# design.net
KiCad netlist of a schematic drawn in EasyEDA Pro
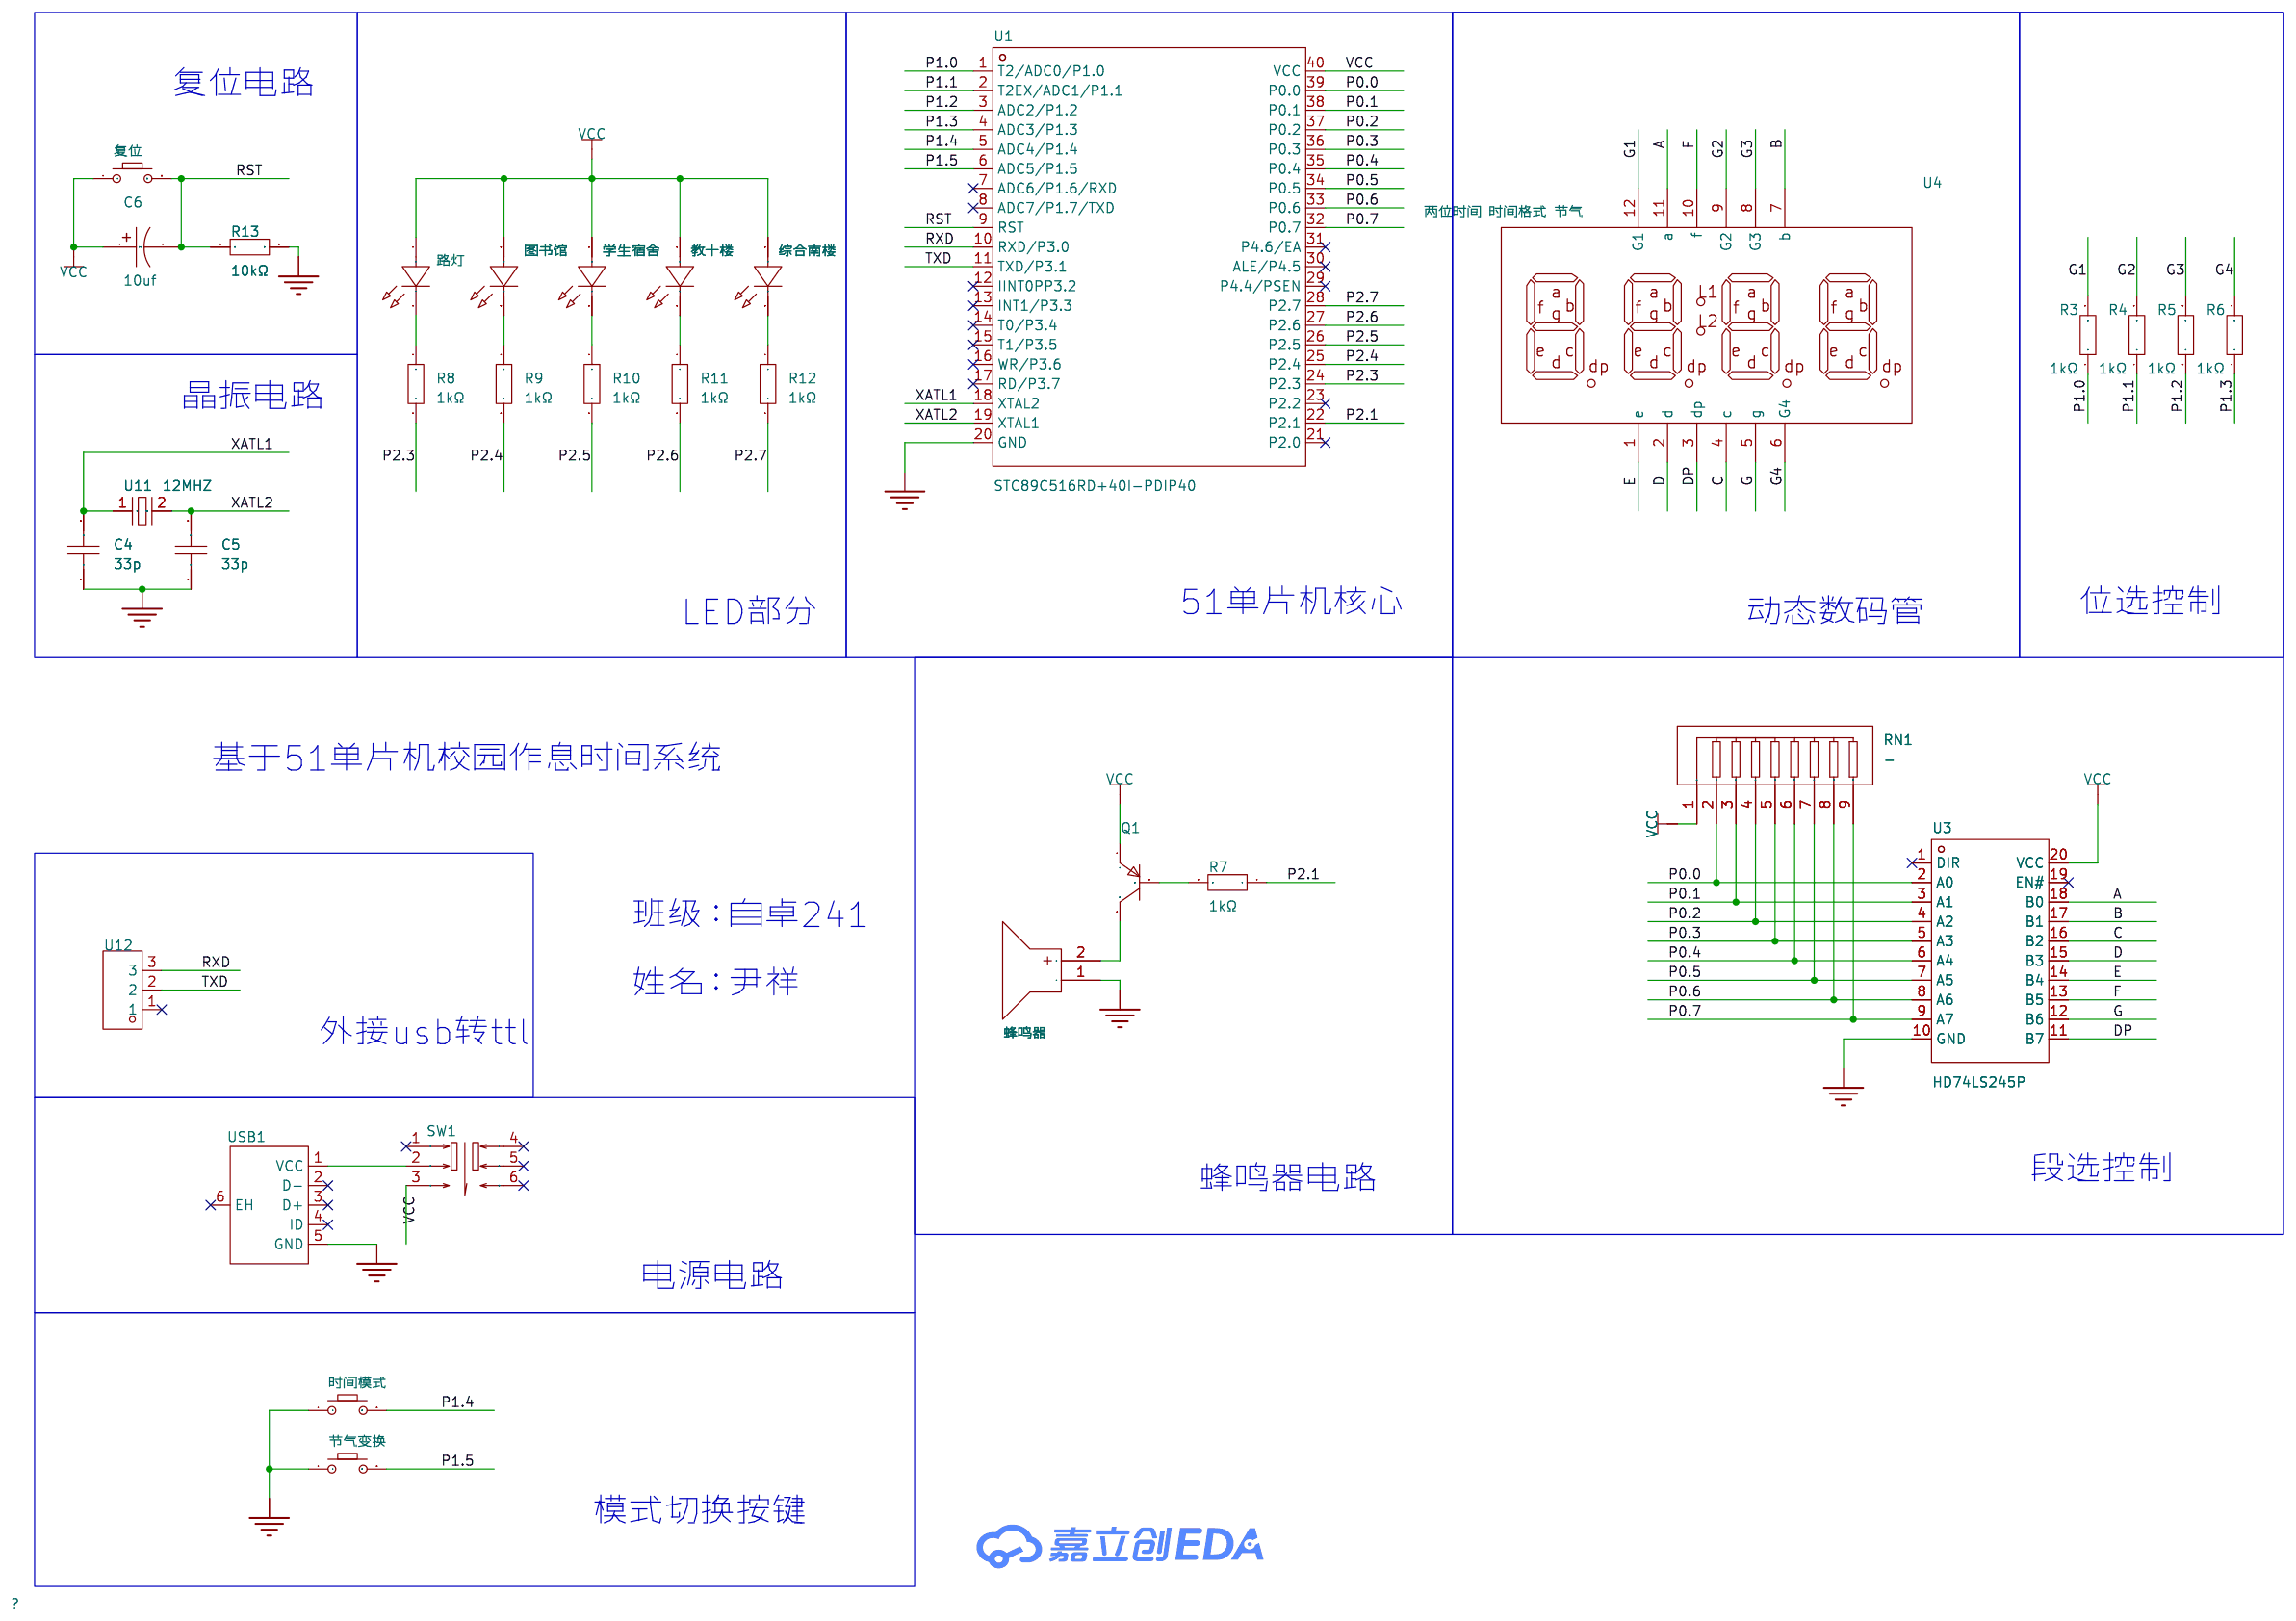
[diagram p0: schematic sheet]

(export (version "E")
  (design (tool "Eeschema 10.0.6"))
  (components
    (comp (ref "C4")
      (value "33p")
      (footprint "easyedapro:CAP-TH_L10.0-W4.5-P7.50-D0.6")
      (description "容值:-;额定电压:-;")
      (fields (field (name "Manufacturer Part") "250V 0.1uF 5% CBB电容"))
      (libsource (lib "easyedapro") (part "250V 0.1UF 5% CBBCapacitor"))
    )
    (comp (ref "C5")
      (value "33p")
      (footprint "easyedapro:CAP-TH_L10.0-W4.5-P7.50-D0.6")
      (description "容值:-;额定电压:-;")
      (fields (field (name "Manufacturer Part") "250V 0.1uF 5% CBB电容"))
      (libsource (lib "easyedapro") (part "250V 0.1UF 5% CBBCapacitor"))
    )
    (comp (ref "C6")
      (value "10uf")
      (footprint "easyedapro:CAP-TH_BD10.0-P5.00-D0.6-FD")
      (libsource (lib "easyedapro") (part "LF221M1HBKJ1013VGN"))
    )
    (comp (ref "Q1")
      (value "~")
      (footprint "easyedapro:S8550P_TO-92")
      (libsource (lib "easyedapro") (part "S8550_TO_PNP"))
    )
    (comp (ref "R3") (value "1kΩ") (footprint "easyedapro:R0603") (libsource (lib "easyedapro") (part "电阻")))
    (comp (ref "R4") (value "1kΩ") (footprint "easyedapro:R0603") (libsource (lib "easyedapro") (part "电阻")))
    (comp (ref "R5") (value "1kΩ") (footprint "easyedapro:R0603") (libsource (lib "easyedapro") (part "电阻")))
    (comp (ref "R6") (value "1kΩ") (footprint "easyedapro:R0603") (libsource (lib "easyedapro") (part "电阻")))
    (comp (ref "R7") (value "1kΩ") (footprint "easyedapro:R0603") (libsource (lib "easyedapro") (part "电阻")))
    (comp (ref "R8") (value "1kΩ") (footprint "easyedapro:R0603") (libsource (lib "easyedapro") (part "电阻")))
    (comp (ref "R9") (value "1kΩ") (footprint "easyedapro:R0603") (libsource (lib "easyedapro") (part "电阻")))
    (comp (ref "R10") (value "1kΩ") (footprint "easyedapro:R0603") (libsource (lib "easyedapro") (part "电阻")))
    (comp (ref "R11") (value "1kΩ") (footprint "easyedapro:R0603") (libsource (lib "easyedapro") (part "电阻")))
    (comp (ref "R12") (value "1kΩ") (footprint "easyedapro:R0603") (libsource (lib "easyedapro") (part "电阻")))
    (comp (ref "R13")
      (value "10kΩ")
      (footprint "easyedapro:R0603")
      (libsource (lib "easyedapro") (part "电阻"))
    )
    (comp (ref "RN1")
      (value "-")
      (footprint "easyedapro:RES-ARRAY-TH_9P-P2.54-D1.0")
      (description "电阻器数:-;阻值:-;单个元件功率:-;")
      (fields (field (name "Manufacturer Part") "排阻 10 K 5%"))
      (libsource (lib "easyedapro") (part "10 K 5%"))
    )
    (comp (ref "SW1")
      (value "SP-2212")
      (footprint "easyedapro:SW-TH_6P-L7.2-W7.2-P2.00-LS5.0")
      (description "电路结构:双刀双掷;自锁/无锁:自锁;安装方式:直插;触点电流:100mA;额定电压 (DC):30V;作用力:230gf;机械寿命:1.2万次;")
      (fields (field (name "Manufacturer") "RISHENG(日昇)"))
      (libsource (lib "easyedapro") (part "SP-2212"))
    )
    (comp (ref "U1")
      (value "STC89C516RD+40I-PDIP40")
      (footprint "easyedapro:DIP-40_L52.3-W13.9-P2.54-LS15.2-BL")
      (description "CPU内核:51系列;程序存储容量:61KB;RAM总容量:1.25KB;GPIO端口数量:35;工作电压范围:3.5V~5.5V;CPU最大主频:-;程序存储器类型:FLASH;")
      (fields (field (name "Manufacturer") "STC(宏晶)"))
      (libsource (lib "easyedapro") (part "STC89C516RD+40I-PDIP40"))
    )
    (comp (ref "U3")
      (value "HD74LS245P")
      (footprint "easyedapro:DIP-20_L26.8-W6.4-P2.54-LS7.6-BL")
      (fields (field (name "Manufacturer") "RENESAS(瑞萨)/IDT"))
      (libsource (lib "easyedapro") (part "HD74LS245P"))
    )
    (comp (ref "U4")
      (value "两位时间 时间格式 节气")
      (footprint "easyedapro:LED-SEG-TH_12P-L32.1-W10.0-P12.7-S7.62-BL")
      (libsource (lib "easyedapro") (part "0.28 4位 数码管"))
    )
    (comp (ref "U11")
      (value "12MHZ")
      (footprint "easyedapro:HC-49S_L11.0-W4.7-P4.88")
      (libsource (lib "easyedapro") (part "直插晶振"))
    )
    (comp (ref "U12")
      (value "2.54MM间距单排插针3P/高度11mm")
      (footprint "easyedapro:HDR-TH_3P-P2.54-V-M")
      (libsource (lib "easyedapro") (part "2.54MM间距单排插针3P/高度11MM"))
    )
    (comp (ref "USB1")
      (value "~")
      (footprint "easyedapro:USB_Micro")
      (libsource (lib "easyedapro") (part "USB_Micro"))
    )
    (comp (ref "图书馆")
      (value "图书馆")
      (footprint "easyedapro:LED-TH_BD3.0-P2.54-FD")
      (libsource (lib "easyedapro") (part "3MMFIR"))
    )
    (comp (ref "复位")
      (value "~")
      (footprint "easyedapro:Key_TH_3.5x6x4.3")
      (libsource (lib "easyedapro") (part "Key_TH_3.5x6x4.3"))
    )
    (comp (ref "学生宿舍")
      (value "学生宿舍")
      (footprint "easyedapro:LED-TH_BD3.0-P2.54-FD")
      (libsource (lib "easyedapro") (part "3MMFIR"))
    )
    (comp (ref "打铃")
      (value "蜂鸣器")
      (footprint "easyedapro:BUZ-TH_BD12.0-P6.00-D0.9-RD")
      (fields (field (name "Manufacturer Part") "打铃"))
      (libsource (lib "easyedapro") (part "BUZZER"))
    )
    (comp (ref "教十楼")
      (value "教十楼")
      (footprint "easyedapro:LED-TH_BD3.0-P2.54-FD")
      (libsource (lib "easyedapro") (part "3MMFIR"))
    )
    (comp (ref "时间模式")
      (value "~")
      (footprint "easyedapro:Key_TH_3.5x6x4.3")
      (libsource (lib "easyedapro") (part "Key_TH_3.5x6x4.3"))
    )
    (comp (ref "综合南楼")
      (value "综合南楼")
      (footprint "easyedapro:LED-TH_BD3.0-P2.54-FD")
      (libsource (lib "easyedapro") (part "3MMFIR"))
    )
    (comp (ref "节气变换")
      (value "~")
      (footprint "easyedapro:Key_TH_3.5x6x4.3")
      (libsource (lib "easyedapro") (part "Key_TH_3.5x6x4.3"))
    )
    (comp (ref "路灯")
      (value "路灯")
      (footprint "easyedapro:LED-TH_BD3.0-P2.54-FD")
      (libsource (lib "easyedapro") (part "3MMFIR"))
    )
  )
  (nets
    (net (code "1") (name "/A") (class "Default")
      (node (ref "U3") (pin "18") (pinfunction "B0_18") (pintype "unspecified"))
      (node (ref "U4") (pin "11") (pinfunction "a_11") (pintype "input"))
    )
    (net (code "2") (name "/B") (class "Default")
      (node (ref "U3") (pin "17") (pinfunction "B1_17") (pintype "unspecified"))
      (node (ref "U4") (pin "7") (pinfunction "b_7") (pintype "input"))
    )
    (net (code "3") (name "/C") (class "Default")
      (node (ref "U3") (pin "16") (pinfunction "B2_16") (pintype "unspecified"))
      (node (ref "U4") (pin "4") (pinfunction "c_4") (pintype "input"))
    )
    (net (code "4") (name "/D") (class "Default")
      (node (ref "U3") (pin "15") (pinfunction "B3_15") (pintype "unspecified"))
      (node (ref "U4") (pin "2") (pinfunction "d_2") (pintype "input"))
    )
    (net (code "5") (name "/DP") (class "Default")
      (node (ref "U3") (pin "11") (pinfunction "B7_11") (pintype "unspecified"))
      (node (ref "U4") (pin "3") (pinfunction "dp_3") (pintype "input"))
    )
    (net (code "6") (name "/E") (class "Default")
      (node (ref "U3") (pin "14") (pinfunction "B4_14") (pintype "unspecified"))
      (node (ref "U4") (pin "1") (pinfunction "e_1") (pintype "input"))
    )
    (net (code "7") (name "/F") (class "Default")
      (node (ref "U3") (pin "13") (pinfunction "B5_13") (pintype "unspecified"))
      (node (ref "U4") (pin "10") (pinfunction "f_10") (pintype "input"))
    )
    (net (code "8") (name "/G") (class "Default")
      (node (ref "U3") (pin "12") (pinfunction "B6_12") (pintype "unspecified"))
      (node (ref "U4") (pin "5") (pinfunction "g_5") (pintype "input"))
    )
    (net (code "9") (name "/G1") (class "Default")
      (node (ref "R3") (pin "2") (pinfunction "2_2") (pintype "input"))
      (node (ref "U4") (pin "12") (pinfunction "G1_12") (pintype "input"))
    )
    (net (code "10") (name "/G2") (class "Default")
      (node (ref "R4") (pin "2") (pinfunction "2_2") (pintype "input"))
      (node (ref "U4") (pin "9") (pinfunction "G2_9") (pintype "input"))
    )
    (net (code "11") (name "/G3") (class "Default")
      (node (ref "R5") (pin "2") (pinfunction "2_2") (pintype "input"))
      (node (ref "U4") (pin "8") (pinfunction "G3_8") (pintype "input"))
    )
    (net (code "12") (name "/G4") (class "Default")
      (node (ref "R6") (pin "2") (pinfunction "2_2") (pintype "input"))
      (node (ref "U4") (pin "6") (pinfunction "G4_6") (pintype "input"))
    )
    (net (code "13") (name "/P0.0") (class "Default")
      (node (ref "RN1") (pin "2") (pinfunction "2_2") (pintype "input"))
      (node (ref "U1") (pin "39") (pinfunction "P0.0_39") (pintype "unspecified"))
      (node (ref "U3") (pin "2") (pinfunction "A0_2") (pintype "unspecified"))
    )
    (net (code "14") (name "/P0.1") (class "Default")
      (node (ref "RN1") (pin "3") (pinfunction "3_3") (pintype "input"))
      (node (ref "U1") (pin "38") (pinfunction "P0.1_38") (pintype "unspecified"))
      (node (ref "U3") (pin "3") (pinfunction "A1_3") (pintype "unspecified"))
    )
    (net (code "15") (name "/P0.2") (class "Default")
      (node (ref "RN1") (pin "4") (pinfunction "4_4") (pintype "input"))
      (node (ref "U1") (pin "37") (pinfunction "P0.2_37") (pintype "unspecified"))
      (node (ref "U3") (pin "4") (pinfunction "A2_4") (pintype "unspecified"))
    )
    (net (code "16") (name "/P0.3") (class "Default")
      (node (ref "RN1") (pin "5") (pinfunction "5_5") (pintype "input"))
      (node (ref "U1") (pin "36") (pinfunction "P0.3_36") (pintype "unspecified"))
      (node (ref "U3") (pin "5") (pinfunction "A3_5") (pintype "unspecified"))
    )
    (net (code "17") (name "/P0.4") (class "Default")
      (node (ref "RN1") (pin "6") (pinfunction "6_6") (pintype "input"))
      (node (ref "U1") (pin "35") (pinfunction "P0.4_35") (pintype "unspecified"))
      (node (ref "U3") (pin "6") (pinfunction "A4_6") (pintype "unspecified"))
    )
    (net (code "18") (name "/P0.5") (class "Default")
      (node (ref "RN1") (pin "7") (pinfunction "7_7") (pintype "input"))
      (node (ref "U1") (pin "34") (pinfunction "P0.5_34") (pintype "unspecified"))
      (node (ref "U3") (pin "7") (pinfunction "A5_7") (pintype "unspecified"))
    )
    (net (code "19") (name "/P0.6") (class "Default")
      (node (ref "RN1") (pin "8") (pinfunction "8_8") (pintype "input"))
      (node (ref "U1") (pin "33") (pinfunction "P0.6_33") (pintype "unspecified"))
      (node (ref "U3") (pin "8") (pinfunction "A6_8") (pintype "unspecified"))
    )
    (net (code "20") (name "/P0.7") (class "Default")
      (node (ref "RN1") (pin "9") (pinfunction "9_9") (pintype "input"))
      (node (ref "U1") (pin "32") (pinfunction "P0.7_32") (pintype "unspecified"))
      (node (ref "U3") (pin "9") (pinfunction "A7_9") (pintype "unspecified"))
    )
    (net (code "21") (name "/P1.0") (class "Default")
      (node (ref "R3") (pin "1") (pinfunction "1_1") (pintype "input"))
      (node (ref "U1") (pin "1") (pinfunction "T2/ADC0/P1.0_1") (pintype "unspecified"))
    )
    (net (code "22") (name "/P1.1") (class "Default")
      (node (ref "R4") (pin "1") (pinfunction "1_1") (pintype "input"))
      (node (ref "U1") (pin "2") (pinfunction "T2EX/ADC1/P1.1_2") (pintype "unspecified"))
    )
    (net (code "23") (name "/P1.2") (class "Default")
      (node (ref "R5") (pin "1") (pinfunction "1_1") (pintype "input"))
      (node (ref "U1") (pin "3") (pinfunction "ADC2/P1.2_3") (pintype "unspecified"))
    )
    (net (code "24") (name "/P1.3") (class "Default")
      (node (ref "R6") (pin "1") (pinfunction "1_1") (pintype "input"))
      (node (ref "U1") (pin "4") (pinfunction "ADC3/P1.3_4") (pintype "unspecified"))
    )
    (net (code "25") (name "/P1.4") (class "Default")
      (node (ref "U1") (pin "5") (pinfunction "ADC4/P1.4_5") (pintype "unspecified"))
      (node (ref "时间模式") (pin "B") (pinfunction "B_B") (pintype "input"))
    )
    (net (code "26") (name "/P1.5") (class "Default")
      (node (ref "U1") (pin "6") (pinfunction "ADC5/P1.5_6") (pintype "unspecified"))
      (node (ref "节气变换") (pin "B") (pinfunction "B_B") (pintype "input"))
    )
    (net (code "27") (name "/P2.1") (class "Default")
      (node (ref "R7") (pin "1") (pinfunction "1_1") (pintype "input"))
      (node (ref "U1") (pin "22") (pinfunction "P2.1_22") (pintype "unspecified"))
    )
    (net (code "28") (name "/P2.3") (class "Default")
      (node (ref "R8") (pin "2") (pinfunction "2_2") (pintype "input"))
      (node (ref "U1") (pin "24") (pinfunction "P2.3_24") (pintype "unspecified"))
    )
    (net (code "29") (name "/P2.4") (class "Default")
      (node (ref "R9") (pin "2") (pinfunction "2_2") (pintype "input"))
      (node (ref "U1") (pin "25") (pinfunction "P2.4_25") (pintype "unspecified"))
    )
    (net (code "30") (name "/P2.5") (class "Default")
      (node (ref "R10") (pin "2") (pinfunction "2_2") (pintype "input"))
      (node (ref "U1") (pin "26") (pinfunction "P2.5_26") (pintype "unspecified"))
    )
    (net (code "31") (name "/P2.6") (class "Default")
      (node (ref "R11") (pin "2") (pinfunction "2_2") (pintype "input"))
      (node (ref "U1") (pin "27") (pinfunction "P2.6_27") (pintype "unspecified"))
    )
    (net (code "32") (name "/P2.7") (class "Default")
      (node (ref "R12") (pin "2") (pinfunction "2_2") (pintype "input"))
      (node (ref "U1") (pin "28") (pinfunction "P2.7_28") (pintype "unspecified"))
    )
    (net (code "33") (name "/RST") (class "Default")
      (node (ref "C6") (pin "2") (pinfunction "2_2") (pintype "unspecified"))
      (node (ref "R13") (pin "1") (pinfunction "1_1") (pintype "input"))
      (node (ref "U1") (pin "9") (pinfunction "RST_9") (pintype "unspecified"))
      (node (ref "复位") (pin "B") (pinfunction "B_B") (pintype "input"))
    )
    (net (code "34") (name "/RXD") (class "Default")
      (node (ref "U1") (pin "10") (pinfunction "RXD/P3.0_10") (pintype "unspecified"))
      (node (ref "U12") (pin "3") (pinfunction "3_3") (pintype "unspecified"))
    )
    (net (code "35") (name "/TXD") (class "Default")
      (node (ref "U1") (pin "11") (pinfunction "TXD/P3.1_11") (pintype "unspecified"))
      (node (ref "U12") (pin "2") (pinfunction "2_2") (pintype "unspecified"))
    )
    (net (code "36") (name "/XATL1") (class "Default")
      (node (ref "C4") (pin "2") (pinfunction "2_2") (pintype "unspecified"))
      (node (ref "U1") (pin "18") (pinfunction "XTAL2_18") (pintype "unspecified"))
      (node (ref "U11") (pin "1") (pinfunction "1_1") (pintype "input"))
    )
    (net (code "37") (name "/XATL2") (class "Default")
      (node (ref "C5") (pin "2") (pinfunction "2_2") (pintype "unspecified"))
      (node (ref "U1") (pin "19") (pinfunction "XTAL1_19") (pintype "unspecified"))
      (node (ref "U11") (pin "2") (pinfunction "GND_2") (pintype "input"))
    )
    (net (code "38") (name "GND") (class "Default")
      (node (ref "C4") (pin "1") (pinfunction "1_1") (pintype "unspecified"))
      (node (ref "C5") (pin "1") (pinfunction "1_1") (pintype "unspecified"))
      (node (ref "R13") (pin "2") (pinfunction "2_2") (pintype "input"))
      (node (ref "U1") (pin "20") (pinfunction "GND_20") (pintype "unspecified"))
      (node (ref "U3") (pin "10") (pinfunction "GND_10") (pintype "unspecified"))
      (node (ref "USB1") (pin "5") (pinfunction "GND_5") (pintype "input"))
      (node (ref "打铃") (pin "1") (pinfunction "-_1") (pintype "unspecified"))
      (node (ref "时间模式") (pin "A") (pinfunction "A_A") (pintype "input"))
      (node (ref "节气变换") (pin "A") (pinfunction "A_A") (pintype "input"))
    )
    (net (code "39") (name "Net-(Q1-B)") (class "Default")
      (node (ref "Q1") (pin "2") (pinfunction "B_2") (pintype "input"))
      (node (ref "R7") (pin "2") (pinfunction "2_2") (pintype "input"))
    )
    (net (code "40") (name "Net-(Q1-C)") (class "Default")
      (node (ref "Q1") (pin "3") (pinfunction "C_3") (pintype "input"))
      (node (ref "打铃") (pin "2") (pinfunction "+_2") (pintype "unspecified"))
    )
    (net (code "41") (name "Net-(USB1-VCC)") (class "Default")
      (node (ref "SW1") (pin "2") (pinfunction "2_2") (pintype "unspecified"))
      (node (ref "USB1") (pin "1") (pinfunction "VCC_1") (pintype "input"))
    )
    (net (code "42") (name "Net-(图书馆-K)") (class "Default")
      (node (ref "R9") (pin "1") (pinfunction "1_1") (pintype "input"))
      (node (ref "图书馆") (pin "2") (pinfunction "K_2") (pintype "unspecified"))
    )
    (net (code "43") (name "Net-(学生宿舍-K)") (class "Default")
      (node (ref "R10") (pin "1") (pinfunction "1_1") (pintype "input"))
      (node (ref "学生宿舍") (pin "2") (pinfunction "K_2") (pintype "unspecified"))
    )
    (net (code "44") (name "Net-(教十楼-K)") (class "Default")
      (node (ref "R11") (pin "1") (pinfunction "1_1") (pintype "input"))
      (node (ref "教十楼") (pin "2") (pinfunction "K_2") (pintype "unspecified"))
    )
    (net (code "45") (name "Net-(综合南楼-K)") (class "Default")
      (node (ref "R12") (pin "1") (pinfunction "1_1") (pintype "input"))
      (node (ref "综合南楼") (pin "2") (pinfunction "K_2") (pintype "unspecified"))
    )
    (net (code "46") (name "Net-(路灯-K)") (class "Default")
      (node (ref "R8") (pin "1") (pinfunction "1_1") (pintype "input"))
      (node (ref "路灯") (pin "2") (pinfunction "K_2") (pintype "unspecified"))
    )
    (net (code "47") (name "VCC") (class "Default")
      (node (ref "C6") (pin "1") (pinfunction "1_1") (pintype "unspecified"))
      (node (ref "Q1") (pin "1") (pinfunction "E_1") (pintype "input"))
      (node (ref "RN1") (pin "1") (pinfunction "1_1") (pintype "input"))
      (node (ref "SW1") (pin "3") (pinfunction "3_3") (pintype "unspecified"))
      (node (ref "U1") (pin "40") (pinfunction "VCC_40") (pintype "unspecified"))
      (node (ref "U3") (pin "20") (pinfunction "VCC_20") (pintype "unspecified"))
      (node (ref "图书馆") (pin "1") (pinfunction "A_1") (pintype "unspecified"))
      (node (ref "复位") (pin "A") (pinfunction "A_A") (pintype "input"))
      (node (ref "学生宿舍") (pin "1") (pinfunction "A_1") (pintype "unspecified"))
      (node (ref "教十楼") (pin "1") (pinfunction "A_1") (pintype "unspecified"))
      (node (ref "综合南楼") (pin "1") (pinfunction "A_1") (pintype "unspecified"))
      (node (ref "路灯") (pin "1") (pinfunction "A_1") (pintype "unspecified"))
    )
    (net (code "48") (name "unconnected-(SW1-Pad1)") (class "Default")
      (node (ref "SW1") (pin "1") (pinfunction "1_1") (pintype "unspecified+no_connect"))
    )
    (net (code "49") (name "unconnected-(SW1-Pad4)") (class "Default")
      (node (ref "SW1") (pin "4") (pinfunction "4_4") (pintype "unspecified+no_connect"))
    )
    (net (code "50") (name "unconnected-(SW1-Pad5)") (class "Default")
      (node (ref "SW1") (pin "5") (pinfunction "5_5") (pintype "unspecified+no_connect"))
    )
    (net (code "51") (name "unconnected-(SW1-Pad6)") (class "Default")
      (node (ref "SW1") (pin "6") (pinfunction "6_6") (pintype "unspecified+no_connect"))
    )
    (net (code "52") (name "unconnected-(U1-ADC6{slash}P1.6{slash}RXD-Pad7)") (class "Default")
      (node (ref "U1") (pin "7") (pinfunction "ADC6/P1.6/RXD_7") (pintype "unspecified+no_connect"))
    )
    (net (code "53") (name "unconnected-(U1-ADC7{slash}P1.7{slash}TXD-Pad8)") (class "Default")
      (node (ref "U1") (pin "8") (pinfunction "ADC7/P1.7/TXD_8") (pintype "unspecified+no_connect"))
    )
    (net (code "54") (name "unconnected-(U1-ALE{slash}P4.5-Pad30)") (class "Default")
      (node (ref "U1") (pin "30") (pinfunction "ALE/P4.5_30") (pintype "unspecified+no_connect"))
    )
    (net (code "55") (name "unconnected-(U1-IINT0PP3.2-Pad12)") (class "Default")
      (node (ref "U1") (pin "12") (pinfunction "IINT0PP3.2_12") (pintype "unspecified+no_connect"))
    )
    (net (code "56") (name "unconnected-(U1-INT1{slash}P3.3-Pad13)") (class "Default")
      (node (ref "U1") (pin "13") (pinfunction "INT1/P3.3_13") (pintype "unspecified+no_connect"))
    )
    (net (code "57") (name "unconnected-(U1-P2.0-Pad21)") (class "Default")
      (node (ref "U1") (pin "21") (pinfunction "P2.0_21") (pintype "unspecified+no_connect"))
    )
    (net (code "58") (name "unconnected-(U1-P2.2-Pad23)") (class "Default")
      (node (ref "U1") (pin "23") (pinfunction "P2.2_23") (pintype "unspecified+no_connect"))
    )
    (net (code "59") (name "unconnected-(U1-P4.4{slash}PSEN-Pad29)") (class "Default")
      (node (ref "U1") (pin "29") (pinfunction "P4.4/PSEN_29") (pintype "unspecified+no_connect"))
    )
    (net (code "60") (name "unconnected-(U1-P4.6{slash}EA-Pad31)") (class "Default")
      (node (ref "U1") (pin "31") (pinfunction "P4.6/EA_31") (pintype "unspecified+no_connect"))
    )
    (net (code "61") (name "unconnected-(U1-RD{slash}P3.7-Pad17)") (class "Default")
      (node (ref "U1") (pin "17") (pinfunction "RD/P3.7_17") (pintype "unspecified+no_connect"))
    )
    (net (code "62") (name "unconnected-(U1-T0{slash}P3.4-Pad14)") (class "Default")
      (node (ref "U1") (pin "14") (pinfunction "T0/P3.4_14") (pintype "unspecified+no_connect"))
    )
    (net (code "63") (name "unconnected-(U1-T1{slash}P3.5-Pad15)") (class "Default")
      (node (ref "U1") (pin "15") (pinfunction "T1/P3.5_15") (pintype "unspecified+no_connect"))
    )
    (net (code "64") (name "unconnected-(U1-WR{slash}P3.6-Pad16)") (class "Default")
      (node (ref "U1") (pin "16") (pinfunction "WR/P3.6_16") (pintype "unspecified+no_connect"))
    )
    (net (code "65") (name "unconnected-(U3-DIR-Pad1)") (class "Default")
      (node (ref "U3") (pin "1") (pinfunction "DIR_1") (pintype "unspecified+no_connect"))
    )
    (net (code "66") (name "unconnected-(U3-EN#-Pad19)") (class "Default")
      (node (ref "U3") (pin "19") (pinfunction "EN#_19") (pintype "unspecified+no_connect"))
    )
    (net (code "67") (name "unconnected-(U12-Pad1)") (class "Default")
      (node (ref "U12") (pin "1") (pinfunction "1_1") (pintype "unspecified+no_connect"))
    )
    (net (code "68") (name "unconnected-(USB1-D+-Pad3)") (class "Default")
      (node (ref "USB1") (pin "3") (pinfunction "D+_3") (pintype "input+no_connect"))
    )
    (net (code "69") (name "unconnected-(USB1-D--Pad2)") (class "Default")
      (node (ref "USB1") (pin "2") (pinfunction "D-_2") (pintype "input+no_connect"))
    )
    (net (code "70") (name "unconnected-(USB1-EH-Pad6)") (class "Default")
      (node (ref "USB1") (pin "6") (pinfunction "EH_6") (pintype "input+no_connect"))
    )
    (net (code "71") (name "unconnected-(USB1-ID-Pad4)") (class "Default")
      (node (ref "USB1") (pin "4") (pinfunction "ID_4") (pintype "input+no_connect"))
    )
  )
)
